# Driver_TS_switch_latch.net
KiCad netlist of a schematic drawn in EAGLE
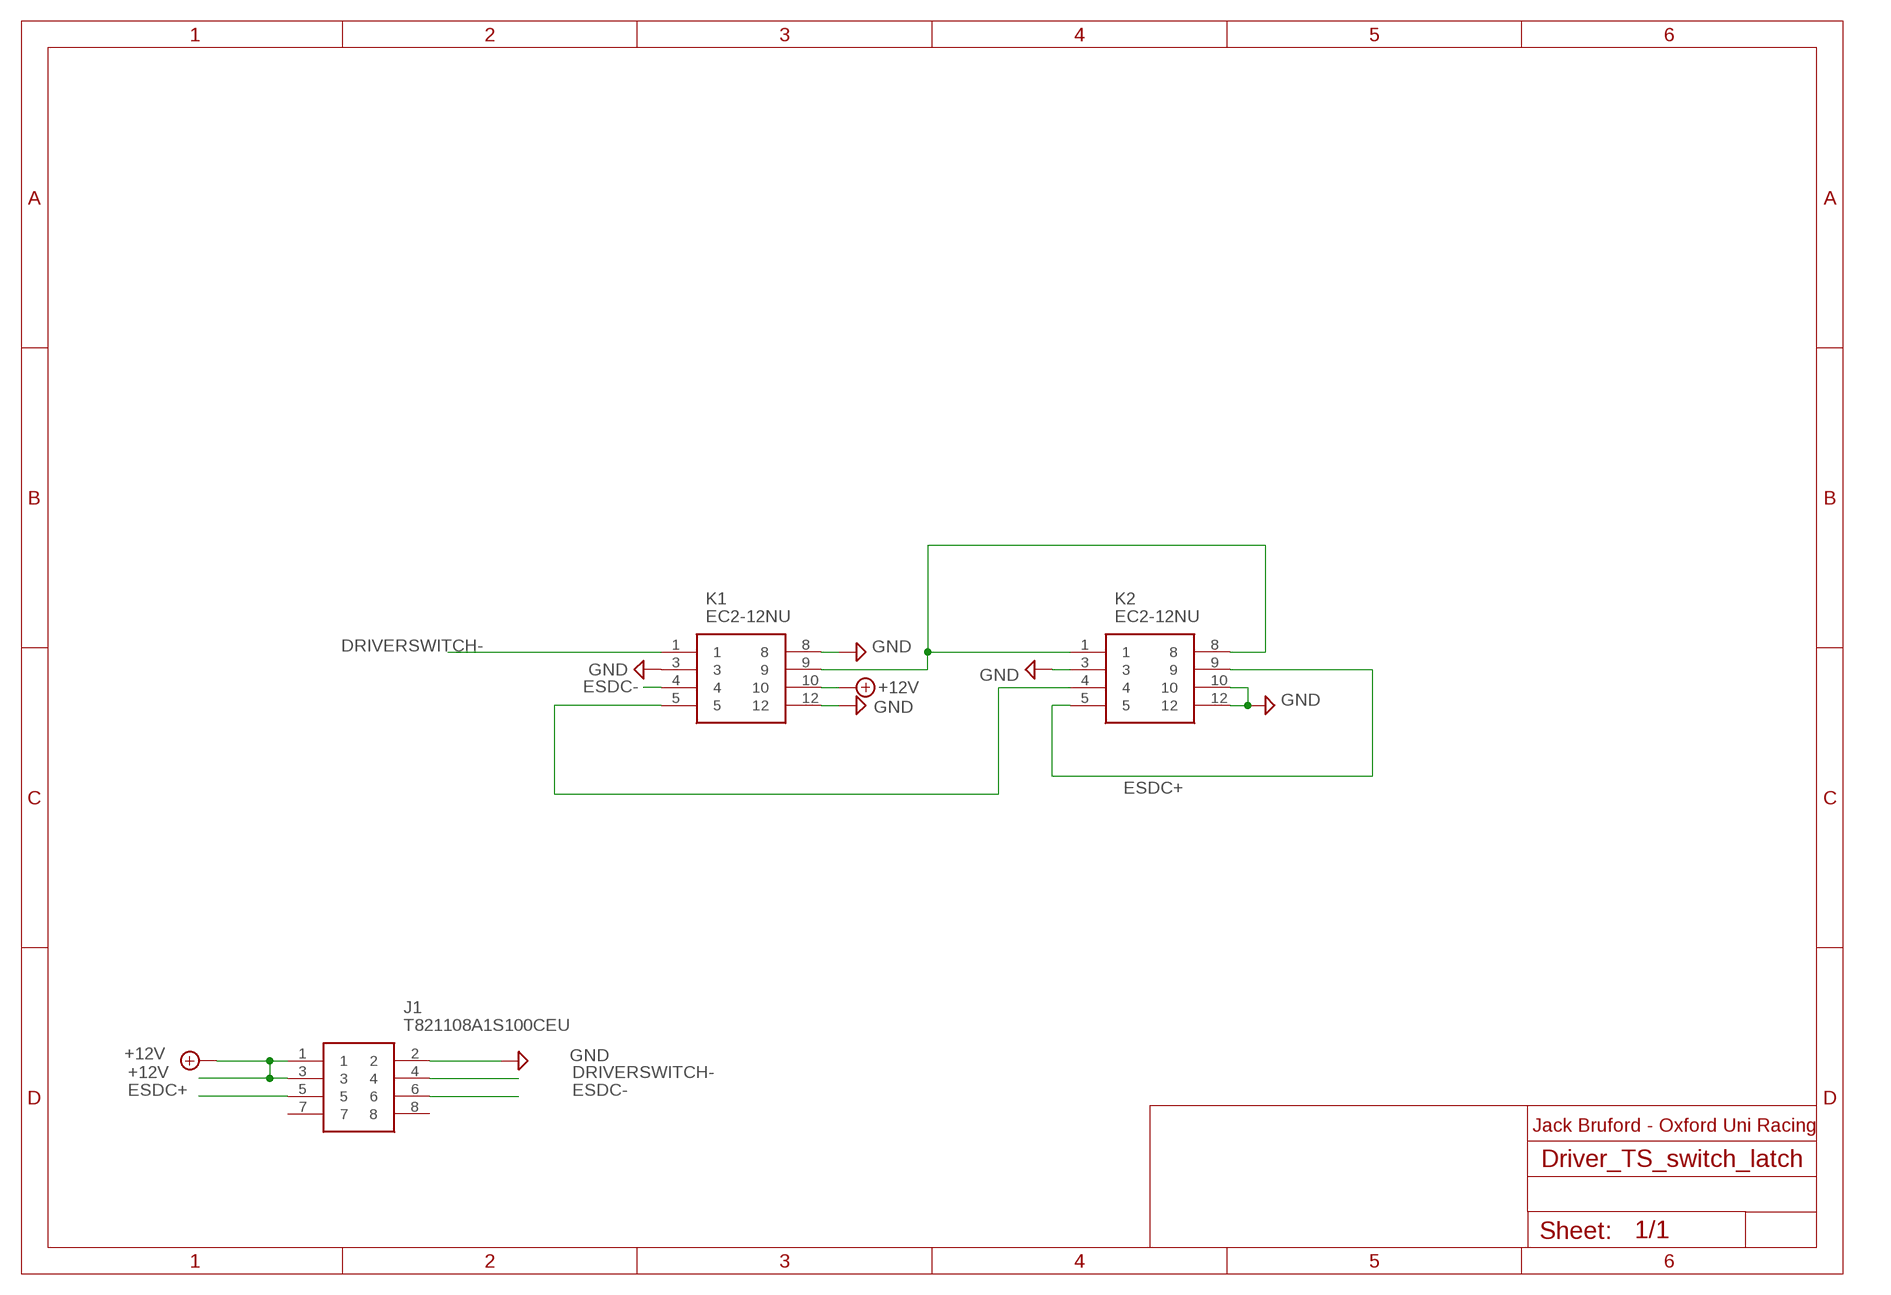
[diagram p0: schematic, sheet 1]

(export (version "E")
  (design (tool "Eeschema 10.0.6"))
  (components
    (comp (ref "J1")
      (value "T821108A1S100CEU")
      (footprint "eagle-import:HDRV8W64P254_2X4_1778X895X915P")
      (fields (field (name "RS_PART_NUMBER") "1702738"))
      (libsource (lib "eagle-import") (part "T821108A1S100CEU"))
    )
    (comp (ref "K1")
      (value "EC2-12NU")
      (footprint "eagle-import:EC2-12NU")
      (fields (field (name "MOUSER_PART_NUMBER") "80-EC2-12NU"))
      (libsource (lib "eagle-import") (part "EC2-12NU"))
    )
    (comp (ref "K2")
      (value "EC2-12NU")
      (footprint "eagle-import:EC2-12NU")
      (fields (field (name "MOUSER_PART_NUMBER") "80-EC2-12NU"))
      (libsource (lib "eagle-import") (part "EC2-12NU"))
    )
  )
  (nets
    (net (code "1") (name "+12V") (class "Default")
      (node (ref "J1") (pin "1") (pinfunction "1_1") (pintype "bidirectional"))
      (node (ref "J1") (pin "3") (pinfunction "3_3") (pintype "bidirectional"))
      (node (ref "K1") (pin "10") (pinfunction "10_10") (pintype "bidirectional"))
    )
    (net (code "2") (name "/DRIVERSWITCH-") (class "Default")
      (node (ref "J1") (pin "4") (pinfunction "4_4") (pintype "bidirectional"))
      (node (ref "K1") (pin "1") (pinfunction "1_1") (pintype "bidirectional"))
    )
    (net (code "3") (name "/ESDC+") (class "Default")
      (node (ref "J1") (pin "5") (pinfunction "5_5") (pintype "bidirectional"))
      (node (ref "K2") (pin "5") (pinfunction "5_5") (pintype "bidirectional"))
      (node (ref "K2") (pin "9") (pinfunction "9_9") (pintype "bidirectional"))
    )
    (net (code "4") (name "/ESDC-") (class "Default")
      (node (ref "J1") (pin "6") (pinfunction "6_6") (pintype "bidirectional"))
      (node (ref "K1") (pin "4") (pinfunction "4_4") (pintype "bidirectional"))
    )
    (net (code "5") (name "GND") (class "Default")
      (node (ref "J1") (pin "2") (pinfunction "2_2") (pintype "bidirectional"))
      (node (ref "K1") (pin "12") (pinfunction "12_12") (pintype "bidirectional"))
      (node (ref "K1") (pin "3") (pinfunction "3_3") (pintype "bidirectional"))
      (node (ref "K1") (pin "8") (pinfunction "8_8") (pintype "bidirectional"))
      (node (ref "K2") (pin "10") (pinfunction "10_10") (pintype "bidirectional"))
      (node (ref "K2") (pin "12") (pinfunction "12_12") (pintype "bidirectional"))
      (node (ref "K2") (pin "3") (pinfunction "3_3") (pintype "bidirectional"))
    )
    (net (code "6") (name "Net-(K1-Pad5)") (class "Default")
      (node (ref "K1") (pin "5") (pinfunction "5_5") (pintype "bidirectional"))
      (node (ref "K2") (pin "4") (pinfunction "4_4") (pintype "bidirectional"))
    )
    (net (code "7") (name "Net-(K1-Pad9)") (class "Default")
      (node (ref "K1") (pin "9") (pinfunction "9_9") (pintype "bidirectional"))
      (node (ref "K2") (pin "1") (pinfunction "1_1") (pintype "bidirectional"))
      (node (ref "K2") (pin "8") (pinfunction "8_8") (pintype "bidirectional"))
    )
    (net (code "8") (name "unconnected-(J1-Pad7)") (class "Default")
      (node (ref "J1") (pin "7") (pinfunction "7_7") (pintype "bidirectional"))
    )
    (net (code "9") (name "unconnected-(J1-Pad8)") (class "Default")
      (node (ref "J1") (pin "8") (pinfunction "8_8") (pintype "bidirectional"))
    )
  )
)
